# NFC_BusinessCard_SilkScreen.net
KiCad netlist of a schematic drawn in EAGLE
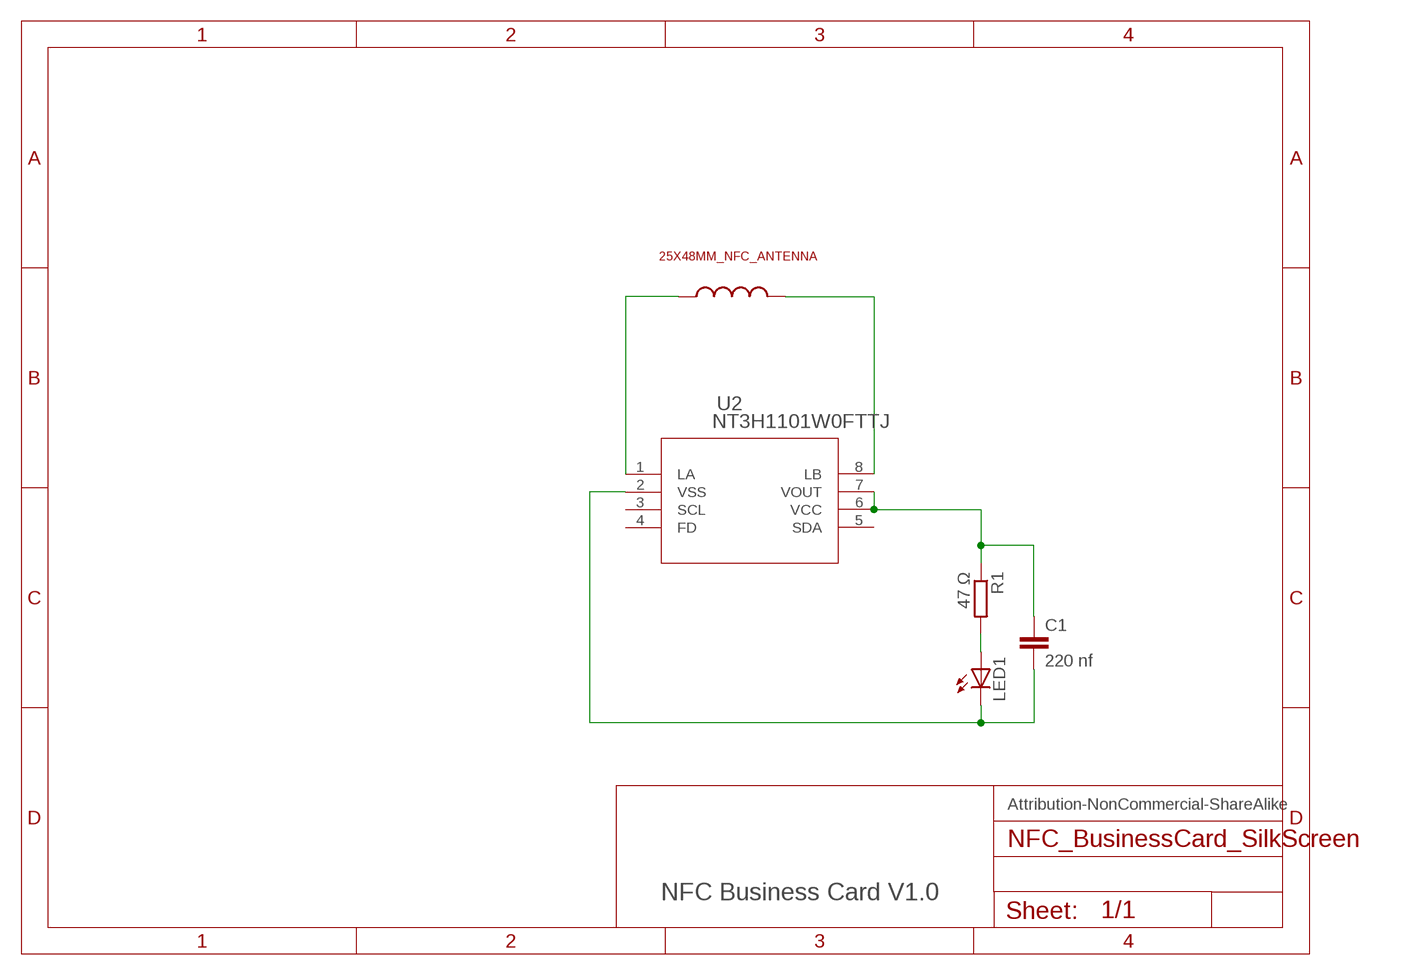
[diagram p0: schematic, sheet 1]

(export (version "E")
  (design (tool "Eeschema 10.0.6"))
  (components
    (comp (ref "ANT")
      (value "25X48MM_NFC_ANTENNA")
      (footprint "eagle-import:25X48MM_NFC")
      (libsource (lib "eagle-import") (part "25X48MM_NFC_ANTENNA"))
    )
    (comp (ref "C1")
      (value "220 nf")
      (footprint "eagle-import:C0603")
      (libsource (lib "eagle-import") (part "C-EUC0603"))
    )
    (comp (ref "LED1")
      (value "LEDSML0805")
      (footprint "eagle-import:SML0805")
      (libsource (lib "eagle-import") (part "LEDSML0805"))
    )
    (comp (ref "R1")
      (value "47 Ω")
      (footprint "eagle-import:R0603")
      (libsource (lib "eagle-import") (part "R-EU_R0603"))
    )
    (comp (ref "U2")
      (value "NT3H1101W0FTTJ")
      (footprint "eagle-import:TSSOP8_SOT505-1_NXP")
      (fields (field (name "COPYRIGHT") "Copyright (C) 2023 Ultra Librarian. All rights reserved."))
      (libsource (lib "eagle-import") (part "NT3H1101W0FTTJ"))
    )
  )
  (nets
    (net (code "1") (name "Net-(LED1-PadA)") (class "Default")
      (node (ref "LED1") (pin "A") (pinfunction "A_A") (pintype "passive"))
      (node (ref "R1") (pin "2") (pinfunction "2_2") (pintype "passive"))
    )
    (net (code "2") (name "Net-(U2-LA)") (class "Default")
      (node (ref "ANT") (pin "P$2") (pinfunction "P$2_P$2") (pintype "bidirectional"))
      (node (ref "U2") (pin "1") (pinfunction "LA_1") (pintype "passive"))
    )
    (net (code "3") (name "Net-(U2-LB)") (class "Default")
      (node (ref "ANT") (pin "P$1") (pinfunction "P$1_P$1") (pintype "bidirectional"))
      (node (ref "U2") (pin "8") (pinfunction "LB_8") (pintype "passive"))
    )
    (net (code "4") (name "Net-(U2-VCC)") (class "Default")
      (node (ref "C1") (pin "1") (pinfunction "1_1") (pintype "passive"))
      (node (ref "R1") (pin "1") (pinfunction "1_1") (pintype "passive"))
      (node (ref "U2") (pin "6") (pinfunction "VCC_6") (pintype "power_in"))
      (node (ref "U2") (pin "7") (pinfunction "VOUT_7") (pintype "power_in"))
    )
    (net (code "5") (name "Net-(U2-VSS)") (class "Default")
      (node (ref "C1") (pin "2") (pinfunction "2_2") (pintype "passive"))
      (node (ref "LED1") (pin "C") (pinfunction "C_C") (pintype "passive"))
      (node (ref "U2") (pin "2") (pinfunction "VSS_2") (pintype "passive"))
    )
    (net (code "6") (name "unconnected-(U2-FD-Pad4)") (class "Default")
      (node (ref "U2") (pin "4") (pinfunction "FD_4") (pintype "passive"))
    )
    (net (code "7") (name "unconnected-(U2-SCL-Pad3)") (class "Default")
      (node (ref "U2") (pin "3") (pinfunction "SCL_3") (pintype "passive"))
    )
    (net (code "8") (name "unconnected-(U2-SDA-Pad5)") (class "Default")
      (node (ref "U2") (pin "5") (pinfunction "SDA_5") (pintype "passive"))
    )
  )
)
